# Mouse_Version_2.net
KiCad netlist of a schematic drawn in EAGLE
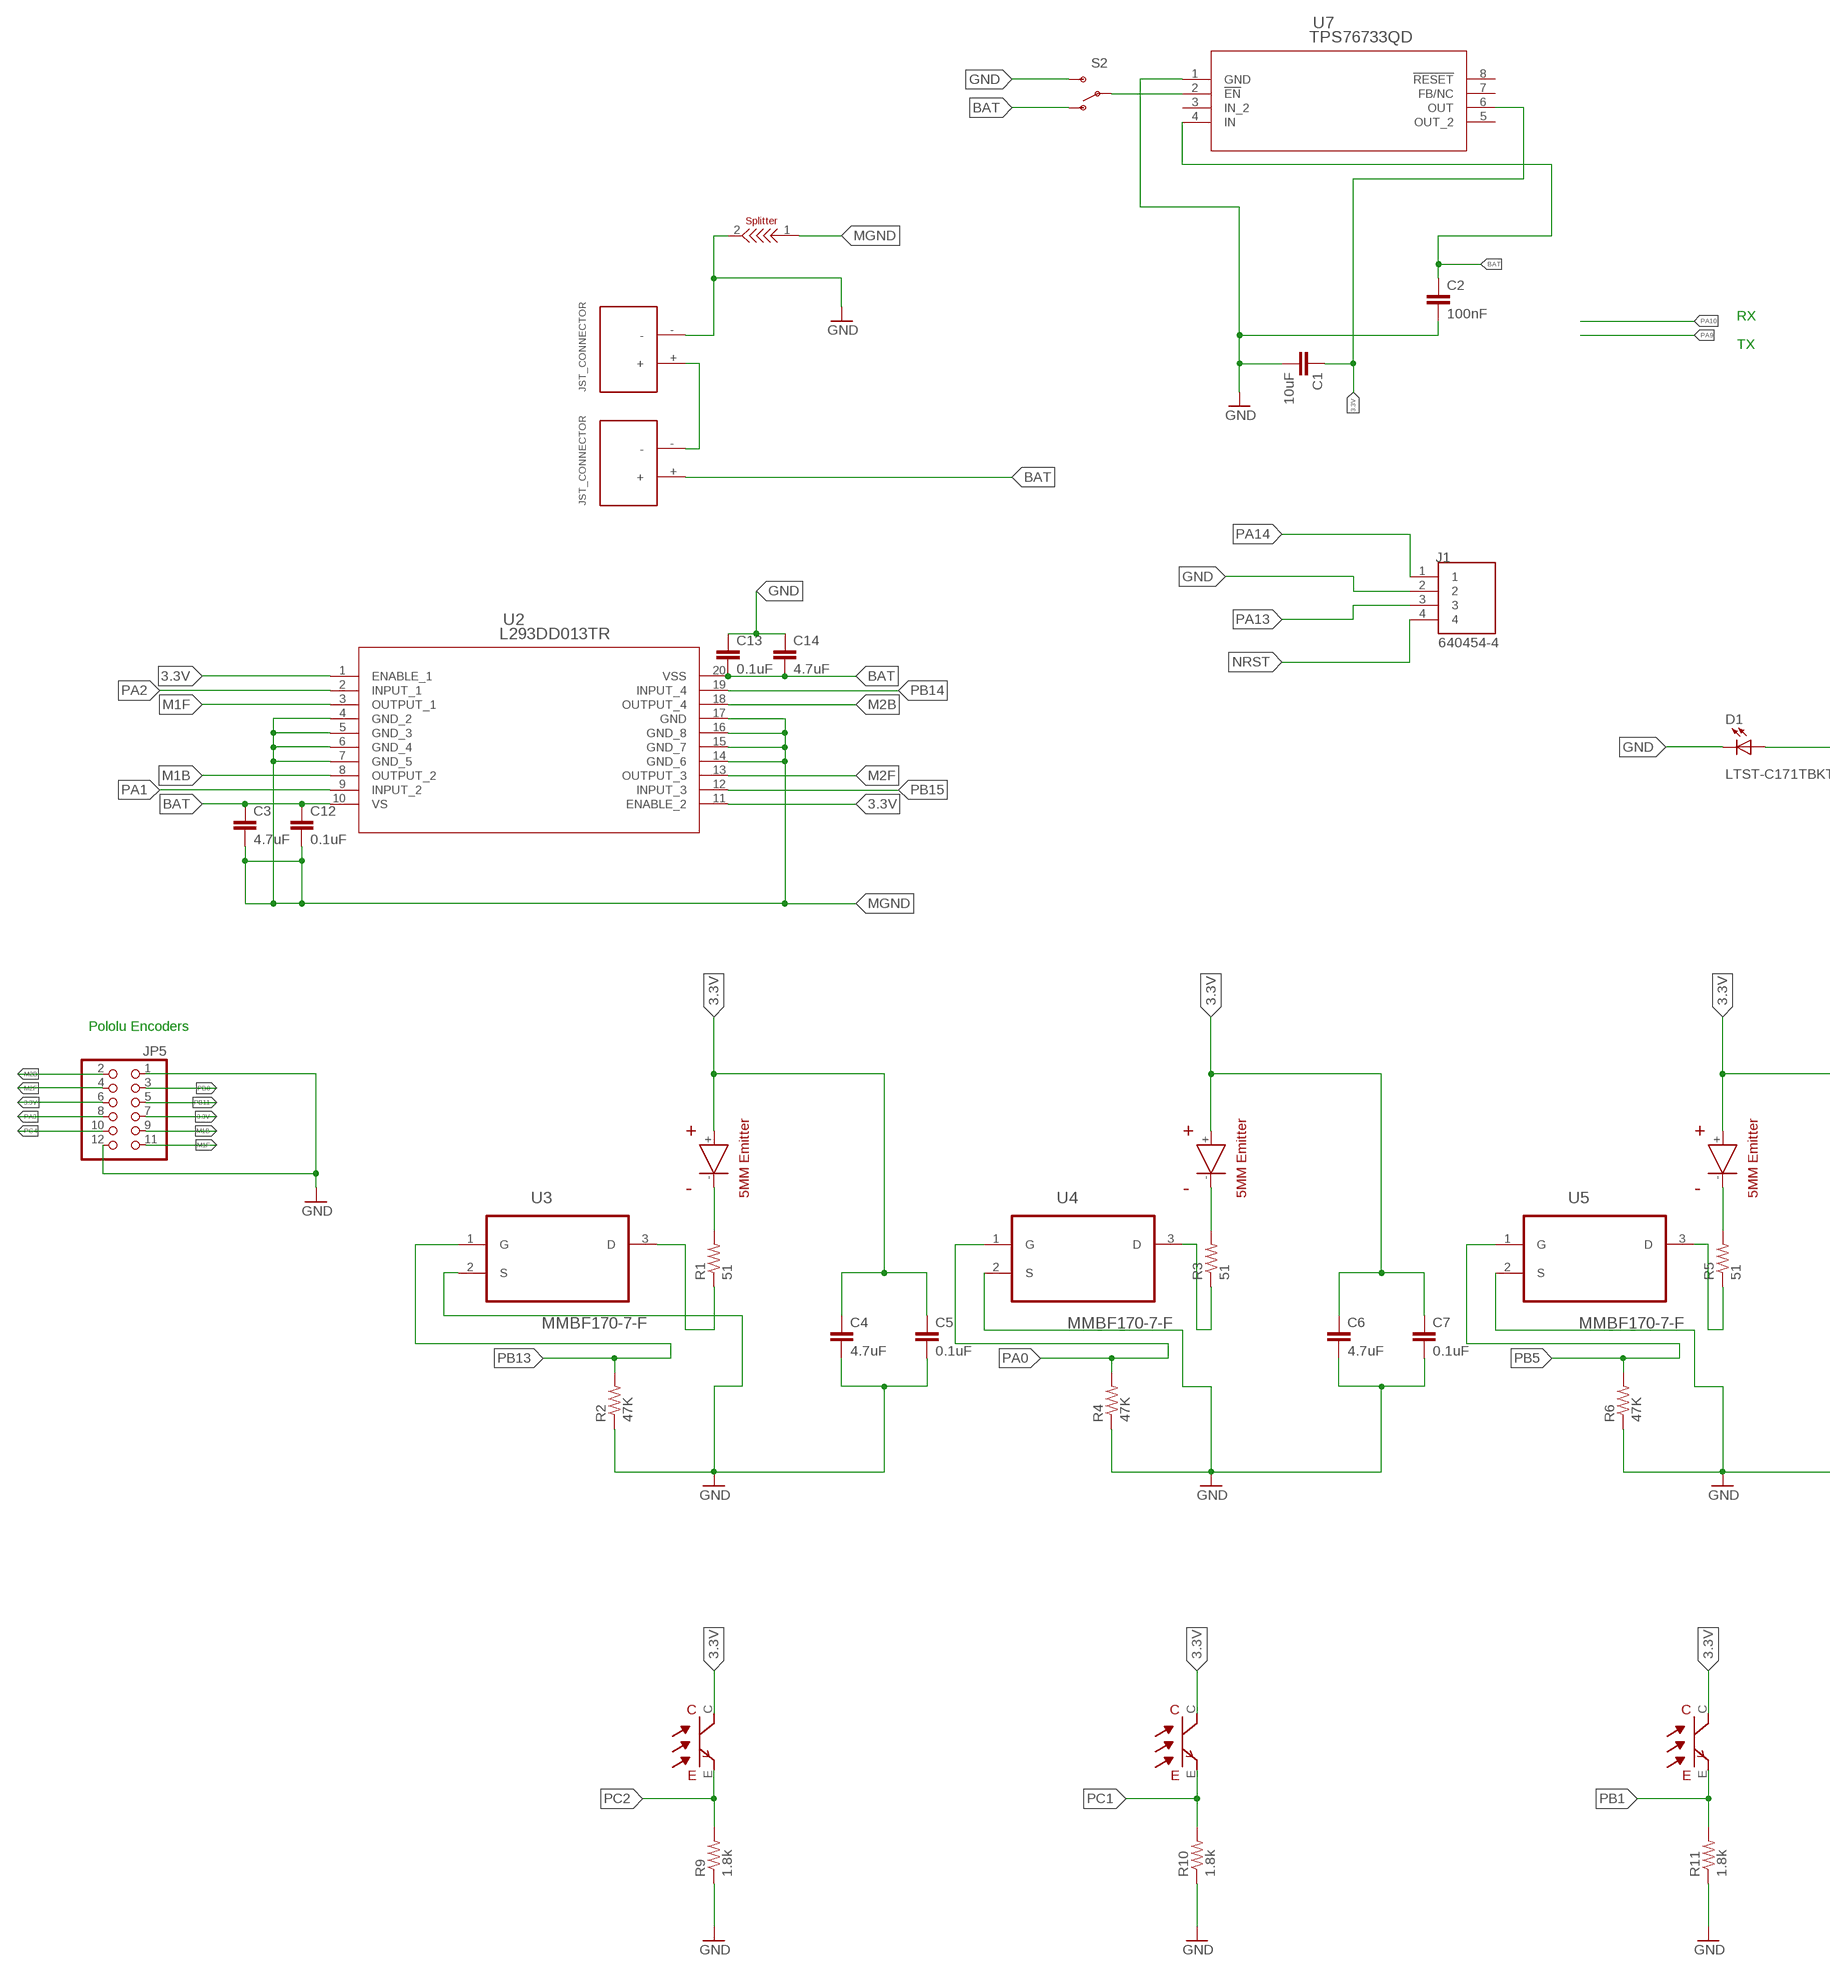
[diagram p0: schematic, sheet 1, part 1 of 2]
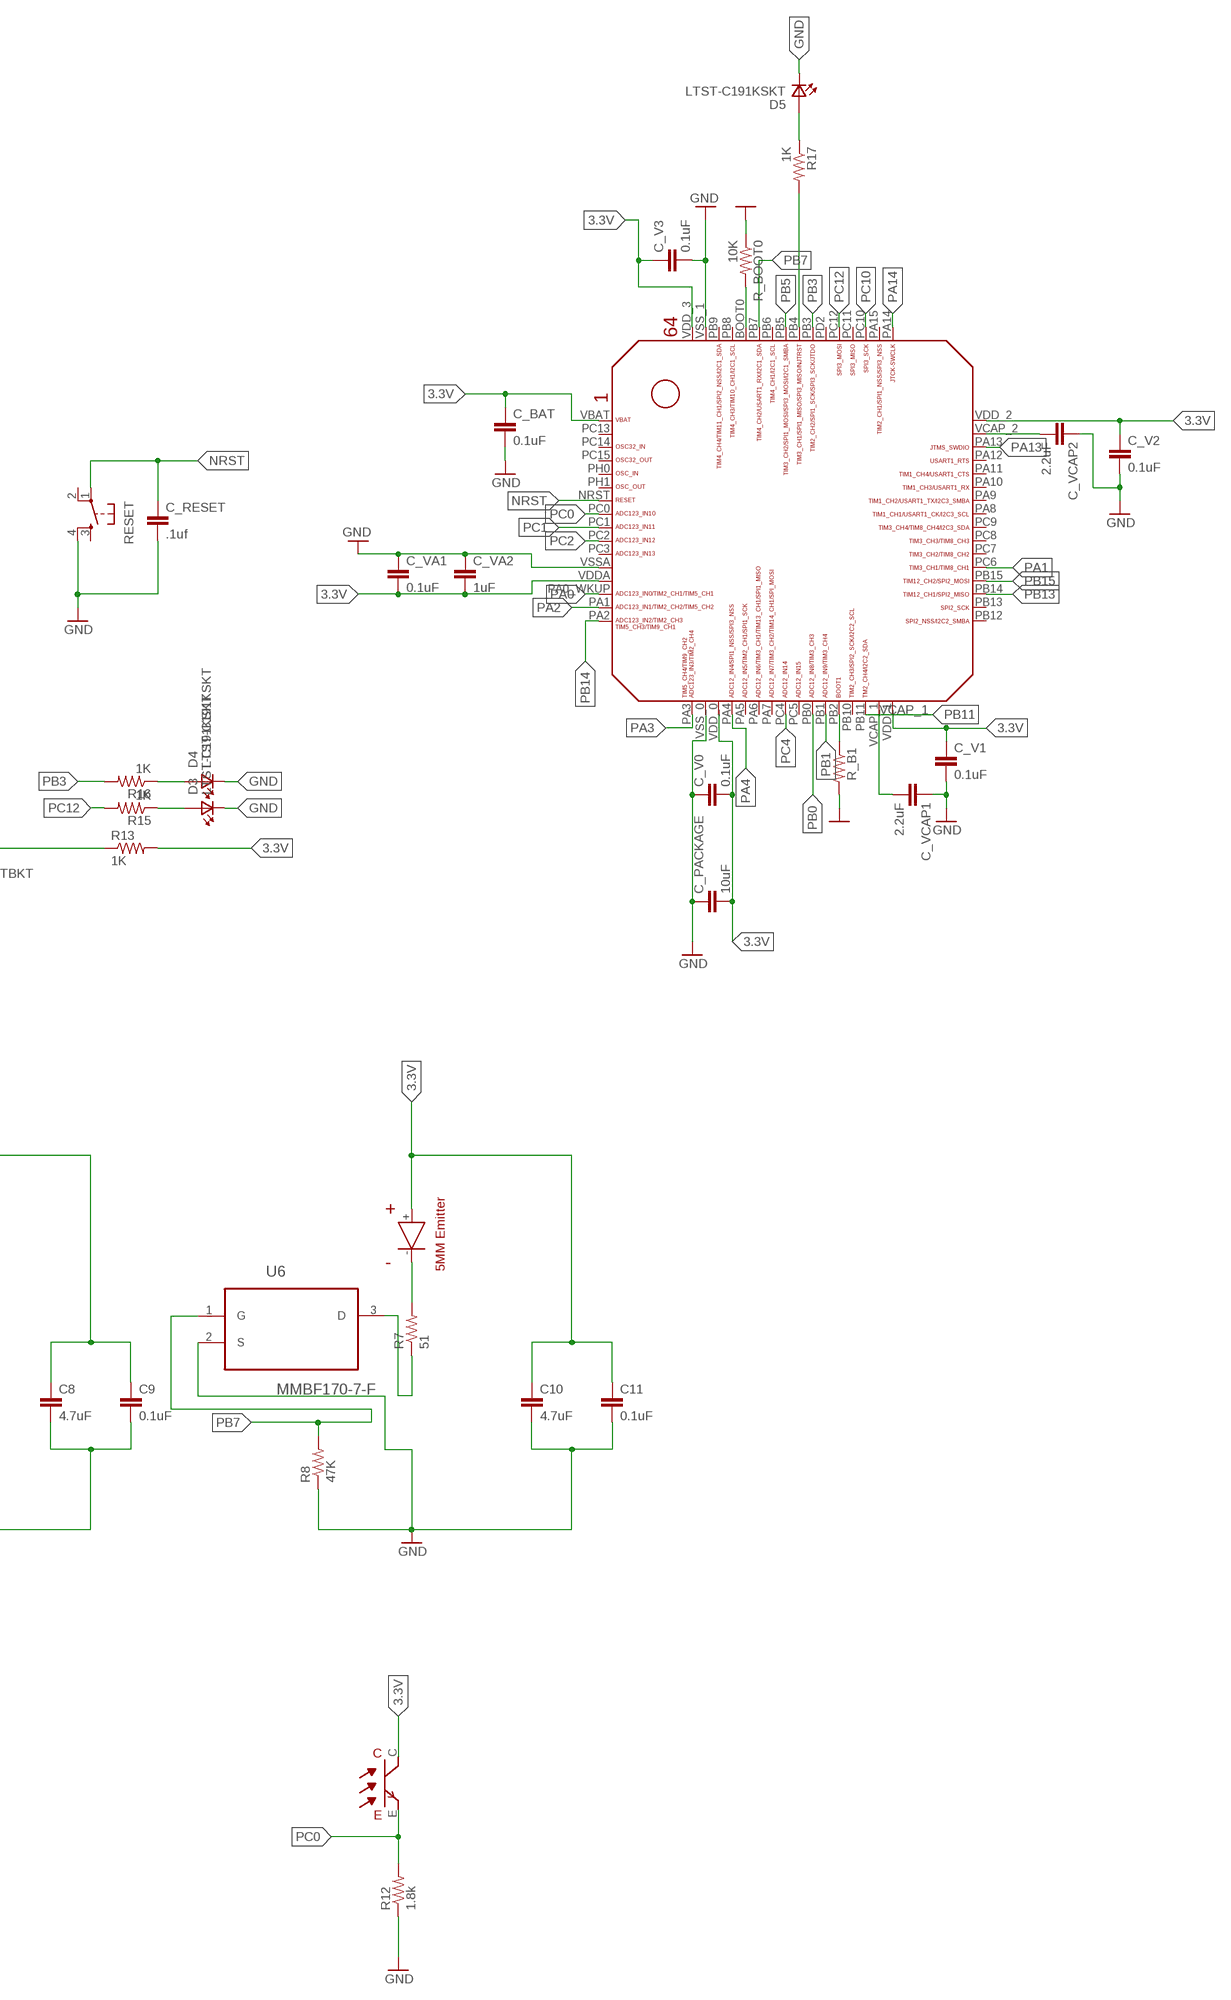
[diagram p1: schematic, sheet 1, part 2 of 2]

(export (version "E")
  (design (tool "Eeschema 10.0.6"))
  (components
    (comp (ref "C1")
      (value "10uF")
      (footprint "eagle-import:0603-CAP")
      (libsource (lib "eagle-import") (part "CAP0603-CAP"))
    )
    (comp (ref "C2")
      (value "100nF")
      (footprint "eagle-import:0603-CAP")
      (libsource (lib "eagle-import") (part "CAP0603-CAP"))
    )
    (comp (ref "C3")
      (value "4.7uF")
      (footprint "eagle-import:0603-CAP")
      (libsource (lib "eagle-import") (part "CAP0603-CAP"))
    )
    (comp (ref "C4")
      (value "4.7uF")
      (footprint "eagle-import:C1206")
      (libsource (lib "eagle-import") (part "C-EUC1206"))
    )
    (comp (ref "C5")
      (value "0.1uF")
      (footprint "eagle-import:C1206")
      (libsource (lib "eagle-import") (part "C-EUC1206"))
    )
    (comp (ref "C6")
      (value "4.7uF")
      (footprint "eagle-import:C1206")
      (libsource (lib "eagle-import") (part "C-EUC1206"))
    )
    (comp (ref "C7")
      (value "0.1uF")
      (footprint "eagle-import:C1206")
      (libsource (lib "eagle-import") (part "C-EUC1206"))
    )
    (comp (ref "C8")
      (value "4.7uF")
      (footprint "eagle-import:C1206")
      (libsource (lib "eagle-import") (part "C-EUC1206"))
    )
    (comp (ref "C9")
      (value "0.1uF")
      (footprint "eagle-import:C1206")
      (libsource (lib "eagle-import") (part "C-EUC1206"))
    )
    (comp (ref "C10")
      (value "4.7uF")
      (footprint "eagle-import:C1206")
      (libsource (lib "eagle-import") (part "C-EUC1206"))
    )
    (comp (ref "C11")
      (value "0.1uF")
      (footprint "eagle-import:C1206")
      (libsource (lib "eagle-import") (part "C-EUC1206"))
    )
    (comp (ref "C12")
      (value "0.1uF")
      (footprint "eagle-import:0603-CAP")
      (libsource (lib "eagle-import") (part "CAP0603-CAP"))
    )
    (comp (ref "C13")
      (value "0.1uF")
      (footprint "eagle-import:0603-CAP")
      (libsource (lib "eagle-import") (part "CAP0603-CAP"))
    )
    (comp (ref "C14")
      (value "4.7uF")
      (footprint "eagle-import:0603-CAP")
      (libsource (lib "eagle-import") (part "CAP0603-CAP"))
    )
    (comp (ref "C_BAT")
      (value "0.1uF")
      (footprint "eagle-import:0603-CAP")
      (libsource (lib "eagle-import") (part "CAP0603-CAP"))
    )
    (comp (ref "C_PACKAGE")
      (value "10uF")
      (footprint "eagle-import:0603-CAP")
      (libsource (lib "eagle-import") (part "CAP0603-CAP"))
    )
    (comp (ref "C_RESET")
      (value ".1uf")
      (footprint "eagle-import:0603")
      (libsource (lib "eagle-import") (part "10NF-0603-50V-10%"))
    )
    (comp (ref "C_V0")
      (value "0.1uF")
      (footprint "eagle-import:0603-CAP")
      (libsource (lib "eagle-import") (part "CAP0603-CAP"))
    )
    (comp (ref "C_V1")
      (value "0.1uF")
      (footprint "eagle-import:0603-CAP")
      (libsource (lib "eagle-import") (part "CAP0603-CAP"))
    )
    (comp (ref "C_V2")
      (value "0.1uF")
      (footprint "eagle-import:0603-CAP")
      (libsource (lib "eagle-import") (part "CAP0603-CAP"))
    )
    (comp (ref "C_V3")
      (value "0.1uF")
      (footprint "eagle-import:0603-CAP")
      (libsource (lib "eagle-import") (part "CAP0603-CAP"))
    )
    (comp (ref "C_VA1")
      (value "0.1uF")
      (footprint "eagle-import:0603-CAP")
      (libsource (lib "eagle-import") (part "CAP0603-CAP"))
    )
    (comp (ref "C_VA2")
      (value "1uF")
      (footprint "eagle-import:0603-CAP")
      (libsource (lib "eagle-import") (part "CAP0603-CAP"))
    )
    (comp (ref "C_VCAP1")
      (value "2.2uF")
      (footprint "eagle-import:0603-CAP")
      (libsource (lib "eagle-import") (part "CAP0603-CAP"))
    )
    (comp (ref "C_VCAP2")
      (value "2.2uF")
      (footprint "eagle-import:0603-CAP")
      (libsource (lib "eagle-import") (part "CAP0603-CAP"))
    )
    (comp (ref "D1")
      (value "LTST-C171TBKT")
      (footprint "eagle-import:DIOC200X125X110")
      (fields (field (name "DIGI-KEY_PART_NUMBER") "160-1645-1-ND") (field (name "MF") "Lite-On Inc."))
      (libsource (lib "eagle-import") (part "LTST-C171TBKT"))
    )
    (comp (ref "D3")
      (value "LTST-C191KSKT")
      (footprint "eagle-import:0603")
      (fields (field (name "DIGI-KEY_PART_NUMBER") "160-1448-1-ND") (field (name "MF") "Lite-On Inc."))
      (libsource (lib "eagle-import") (part "LTST-C191KSKT"))
    )
    (comp (ref "D4")
      (value "LTST-C191KSKT")
      (footprint "eagle-import:0603")
      (fields (field (name "DIGI-KEY_PART_NUMBER") "160-1448-1-ND") (field (name "MF") "Lite-On Inc."))
      (libsource (lib "eagle-import") (part "LTST-C191KSKT"))
    )
    (comp (ref "D5")
      (value "LTST-C191KSKT")
      (footprint "eagle-import:0603")
      (fields (field (name "DIGI-KEY_PART_NUMBER") "160-1448-1-ND") (field (name "MF") "Lite-On Inc."))
      (libsource (lib "eagle-import") (part "LTST-C191KSKT"))
    )
    (comp (ref "J1")
      (value "640454-4")
      (footprint "eagle-import:TE_640454-4")
      (fields (field (name "DIGI-KEY_PART_NUMBER") "A19431-ND") (field (name "MF") "TE Connectivity"))
      (libsource (lib "eagle-import") (part "640454-4"))
    )
    (comp (ref "JP5")
      (value "PINHD-2X6")
      (footprint "eagle-import:2X06")
      (libsource (lib "eagle-import") (part "PINHD-2X6"))
    )
    (comp (ref "R1")
      (value "51")
      (footprint "eagle-import:R0603")
      (libsource (lib "eagle-import") (part "R-US_R0603"))
    )
    (comp (ref "R2")
      (value "47K")
      (footprint "eagle-import:R0603")
      (libsource (lib "eagle-import") (part "R-US_R0603"))
    )
    (comp (ref "R3")
      (value "51")
      (footprint "eagle-import:R0603")
      (libsource (lib "eagle-import") (part "R-US_R0603"))
    )
    (comp (ref "R4")
      (value "47K")
      (footprint "eagle-import:R0603")
      (libsource (lib "eagle-import") (part "R-US_R0603"))
    )
    (comp (ref "R5")
      (value "51")
      (footprint "eagle-import:R0603")
      (libsource (lib "eagle-import") (part "R-US_R0603"))
    )
    (comp (ref "R6")
      (value "47K")
      (footprint "eagle-import:R0603")
      (libsource (lib "eagle-import") (part "R-US_R0603"))
    )
    (comp (ref "R7")
      (value "51")
      (footprint "eagle-import:R0603")
      (libsource (lib "eagle-import") (part "R-US_R0603"))
    )
    (comp (ref "R8")
      (value "47K")
      (footprint "eagle-import:R0603")
      (libsource (lib "eagle-import") (part "R-US_R0603"))
    )
    (comp (ref "R9")
      (value "1.8k")
      (footprint "eagle-import:R0603")
      (libsource (lib "eagle-import") (part "R-US_R0603"))
    )
    (comp (ref "R10")
      (value "1.8k")
      (footprint "eagle-import:R0603")
      (libsource (lib "eagle-import") (part "R-US_R0603"))
    )
    (comp (ref "R11")
      (value "1.8k")
      (footprint "eagle-import:R0603")
      (libsource (lib "eagle-import") (part "R-US_R0603"))
    )
    (comp (ref "R12")
      (value "1.8k")
      (footprint "eagle-import:R0603")
      (libsource (lib "eagle-import") (part "R-US_R0603"))
    )
    (comp (ref "R13")
      (value "1K")
      (footprint "eagle-import:R0603")
      (libsource (lib "eagle-import") (part "R-US_R0603"))
    )
    (comp (ref "R15")
      (value "1K")
      (footprint "eagle-import:R0603")
      (libsource (lib "eagle-import") (part "R-US_R0603"))
    )
    (comp (ref "R16")
      (value "1K")
      (footprint "eagle-import:R0603")
      (libsource (lib "eagle-import") (part "R-US_R0603"))
    )
    (comp (ref "R17")
      (value "1K")
      (footprint "eagle-import:R0603")
      (libsource (lib "eagle-import") (part "R-US_R0603"))
    )
    (comp (ref "RESET")
      (value "TAC_SWITCHPTH")
      (footprint "eagle-import:TACTILE-PTH")
      (libsource (lib "eagle-import") (part "TAC_SWITCHPTH"))
    )
    (comp (ref "R_B1")
      (value "10K")
      (footprint "eagle-import:0603-RES")
      (libsource (lib "eagle-import") (part "RESISTOR0603"))
    )
    (comp (ref "R_BOOT0")
      (value "10K")
      (footprint "eagle-import:0603-RES")
      (libsource (lib "eagle-import") (part "RESISTOR0603"))
    )
    (comp (ref "S2")
      (value "SWITCH-SPSTPTH")
      (footprint "eagle-import:SWITCH-SPDT")
      (libsource (lib "eagle-import") (part "SWITCH-SPSTPTH"))
    )
    (comp (ref "U$1")
      (value "JST_CONNECTOR_FEMALE")
      (footprint "eagle-import:JST_CONNECTOR_FEMALE")
      (libsource (lib "eagle-import") (part "JST_CONNECTOR_FEMALE"))
    )
    (comp (ref "U$2")
      (value "JST_CONNECTOR_FEMALE")
      (footprint "eagle-import:JST_CONNECTOR_FEMALE")
      (libsource (lib "eagle-import") (part "JST_CONNECTOR_FEMALE"))
    )
    (comp (ref "U$3")
      (value "SPLITTER")
      (footprint "eagle-import:SPLITTER")
      (libsource (lib "eagle-import") (part "SPLITTER"))
    )
    (comp (ref "U$4")
      (value "RECEIVER")
      (footprint "eagle-import:RECEIVER")
      (libsource (lib "eagle-import") (part "RECEIVER"))
    )
    (comp (ref "U$5")
      (value "EMITTER")
      (footprint "eagle-import:EMITTER")
      (libsource (lib "eagle-import") (part "EMITTER"))
    )
    (comp (ref "U$6")
      (value "EMITTER")
      (footprint "eagle-import:EMITTER")
      (libsource (lib "eagle-import") (part "EMITTER"))
    )
    (comp (ref "U$7")
      (value "EMITTER")
      (footprint "eagle-import:EMITTER")
      (libsource (lib "eagle-import") (part "EMITTER"))
    )
    (comp (ref "U$8")
      (value "EMITTER")
      (footprint "eagle-import:EMITTER")
      (libsource (lib "eagle-import") (part "EMITTER"))
    )
    (comp (ref "U$9")
      (value "STM32F405/415_LQFP64")
      (footprint "eagle-import:STM32F405_415_LQFP64")
      (libsource (lib "eagle-import") (part "STM32F405/415_LQFP64"))
    )
    (comp (ref "U$15")
      (value "RECEIVER")
      (footprint "eagle-import:RECEIVER")
      (libsource (lib "eagle-import") (part "RECEIVER"))
    )
    (comp (ref "U$18")
      (value "RECEIVER")
      (footprint "eagle-import:RECEIVER")
      (libsource (lib "eagle-import") (part "RECEIVER"))
    )
    (comp (ref "U$19")
      (value "RECEIVER")
      (footprint "eagle-import:RECEIVER")
      (libsource (lib "eagle-import") (part "RECEIVER"))
    )
    (comp (ref "U2")
      (value "L293DD013TR")
      (footprint "eagle-import:SO-20")
      (libsource (lib "eagle-import") (part "L293DD013TR"))
    )
    (comp (ref "U3")
      (value "MMBF170-7-F")
      (footprint "eagle-import:SOT103P240X110-3N")
      (fields (field (name "MF") "Diodes Inc."))
      (libsource (lib "eagle-import") (part "MMBF170-7-F"))
    )
    (comp (ref "U4")
      (value "MMBF170-7-F")
      (footprint "eagle-import:SOT103P240X110-3N")
      (fields (field (name "MF") "Diodes Inc."))
      (libsource (lib "eagle-import") (part "MMBF170-7-F"))
    )
    (comp (ref "U5")
      (value "MMBF170-7-F")
      (footprint "eagle-import:SOT103P240X110-3N")
      (fields (field (name "MF") "Diodes Inc."))
      (libsource (lib "eagle-import") (part "MMBF170-7-F"))
    )
    (comp (ref "U6")
      (value "MMBF170-7-F")
      (footprint "eagle-import:SOT103P240X110-3N")
      (fields (field (name "MF") "Diodes Inc."))
      (libsource (lib "eagle-import") (part "MMBF170-7-F"))
    )
    (comp (ref "U7")
      (value "TPS76733QD")
      (footprint "eagle-import:D8")
      (libsource (lib "eagle-import") (part "TPS76733QD"))
    )
  )
  (nets
    (net (code "1") (name "/VCAP_1") (class "Default")
      (node (ref "C_VCAP1") (pin "2") (pinfunction "2_2") (pintype "passive"))
      (node (ref "U$9") (pin "VCAP_1") (pinfunction "VCAP_1_VCAP_1") (pintype "bidirectional"))
    )
    (net (code "2") (name "3.3V") (class "Default")
      (node (ref "C1") (pin "1") (pinfunction "1_1") (pintype "passive"))
      (node (ref "C10") (pin "1") (pinfunction "1_1") (pintype "passive"))
      (node (ref "C11") (pin "1") (pinfunction "1_1") (pintype "passive"))
      (node (ref "C4") (pin "1") (pinfunction "1_1") (pintype "passive"))
      (node (ref "C5") (pin "1") (pinfunction "1_1") (pintype "passive"))
      (node (ref "C6") (pin "1") (pinfunction "1_1") (pintype "passive"))
      (node (ref "C7") (pin "1") (pinfunction "1_1") (pintype "passive"))
      (node (ref "C8") (pin "1") (pinfunction "1_1") (pintype "passive"))
      (node (ref "C9") (pin "1") (pinfunction "1_1") (pintype "passive"))
      (node (ref "C_BAT") (pin "1") (pinfunction "1_1") (pintype "passive"))
      (node (ref "C_PACKAGE") (pin "2") (pinfunction "2_2") (pintype "passive"))
      (node (ref "C_V0") (pin "2") (pinfunction "2_2") (pintype "passive"))
      (node (ref "C_V1") (pin "1") (pinfunction "1_1") (pintype "passive"))
      (node (ref "C_V2") (pin "1") (pinfunction "1_1") (pintype "passive"))
      (node (ref "C_V3") (pin "1") (pinfunction "1_1") (pintype "passive"))
      (node (ref "C_VA1") (pin "2") (pinfunction "2_2") (pintype "passive"))
      (node (ref "C_VA2") (pin "2") (pinfunction "2_2") (pintype "passive"))
      (node (ref "JP5") (pin "6") (pinfunction "6_6") (pintype "passive"))
      (node (ref "JP5") (pin "7") (pinfunction "7_7") (pintype "passive"))
      (node (ref "R13") (pin "2") (pinfunction "2_2") (pintype "passive"))
      (node (ref "U$15") (pin "C") (pinfunction "C_C") (pintype "bidirectional"))
      (node (ref "U$18") (pin "C") (pinfunction "C_C") (pintype "bidirectional"))
      (node (ref "U$19") (pin "C") (pinfunction "C_C") (pintype "bidirectional"))
      (node (ref "U$4") (pin "C") (pinfunction "C_C") (pintype "bidirectional"))
      (node (ref "U$5") (pin "+") (pinfunction "+_+") (pintype "bidirectional"))
      (node (ref "U$6") (pin "+") (pinfunction "+_+") (pintype "bidirectional"))
      (node (ref "U$7") (pin "+") (pinfunction "+_+") (pintype "bidirectional"))
      (node (ref "U$8") (pin "+") (pinfunction "+_+") (pintype "bidirectional"))
      (node (ref "U$9") (pin "VBAT") (pinfunction "VBAT_VBAT") (pintype "bidirectional"))
      (node (ref "U$9") (pin "VDDA") (pinfunction "VDDA_VDDA") (pintype "bidirectional"))
      (node (ref "U$9") (pin "VDD_0") (pinfunction "VDD_0_VDD_0") (pintype "bidirectional"))
      (node (ref "U$9") (pin "VDD_1") (pinfunction "VDD_1_VDD_1") (pintype "bidirectional"))
      (node (ref "U$9") (pin "VDD_2") (pinfunction "VDD_2_VDD_2") (pintype "bidirectional"))
      (node (ref "U$9") (pin "VDD_3") (pinfunction "VDD_3_VDD_3") (pintype "bidirectional"))
      (node (ref "U2") (pin "1") (pinfunction "ENABLE_1_1") (pintype "input"))
      (node (ref "U2") (pin "11") (pinfunction "ENABLE_2_11") (pintype "input"))
      (node (ref "U7") (pin "6") (pinfunction "OUT_6") (pintype "output"))
    )
    (net (code "3") (name "BAT") (class "Default")
      (node (ref "C12") (pin "1") (pinfunction "1_1") (pintype "passive"))
      (node (ref "C13") (pin "2") (pinfunction "2_2") (pintype "passive"))
      (node (ref "C14") (pin "2") (pinfunction "2_2") (pintype "passive"))
      (node (ref "C2") (pin "1") (pinfunction "1_1") (pintype "passive"))
      (node (ref "C3") (pin "1") (pinfunction "1_1") (pintype "passive"))
      (node (ref "S2") (pin "1") (pinfunction "O_1") (pintype "passive"))
      (node (ref "U$2") (pin "+") (pinfunction "+_+") (pintype "bidirectional"))
      (node (ref "U2") (pin "10") (pinfunction "VS_10") (pintype "passive"))
      (node (ref "U2") (pin "20") (pinfunction "VSS_20") (pintype "passive"))
      (node (ref "U7") (pin "4") (pinfunction "IN_4") (pintype "input"))
    )
    (net (code "4") (name "GND") (class "Default")
      (node (ref "C1") (pin "2") (pinfunction "2_2") (pintype "passive"))
      (node (ref "C10") (pin "2") (pinfunction "2_2") (pintype "passive"))
      (node (ref "C11") (pin "2") (pinfunction "2_2") (pintype "passive"))
      (node (ref "C13") (pin "1") (pinfunction "1_1") (pintype "passive"))
      (node (ref "C14") (pin "1") (pinfunction "1_1") (pintype "passive"))
      (node (ref "C2") (pin "2") (pinfunction "2_2") (pintype "passive"))
      (node (ref "C4") (pin "2") (pinfunction "2_2") (pintype "passive"))
      (node (ref "C5") (pin "2") (pinfunction "2_2") (pintype "passive"))
      (node (ref "C6") (pin "2") (pinfunction "2_2") (pintype "passive"))
      (node (ref "C7") (pin "2") (pinfunction "2_2") (pintype "passive"))
      (node (ref "C8") (pin "2") (pinfunction "2_2") (pintype "passive"))
      (node (ref "C9") (pin "2") (pinfunction "2_2") (pintype "passive"))
      (node (ref "C_BAT") (pin "2") (pinfunction "2_2") (pintype "passive"))
      (node (ref "C_PACKAGE") (pin "1") (pinfunction "1_1") (pintype "passive"))
      (node (ref "C_RESET") (pin "2") (pinfunction "2_2") (pintype "passive"))
      (node (ref "C_V0") (pin "1") (pinfunction "1_1") (pintype "passive"))
      (node (ref "C_V1") (pin "2") (pinfunction "2_2") (pintype "passive"))
      (node (ref "C_V2") (pin "2") (pinfunction "2_2") (pintype "passive"))
      (node (ref "C_V3") (pin "2") (pinfunction "2_2") (pintype "passive"))
      (node (ref "C_VA1") (pin "1") (pinfunction "1_1") (pintype "passive"))
      (node (ref "C_VA2") (pin "1") (pinfunction "1_1") (pintype "passive"))
      (node (ref "C_VCAP1") (pin "1") (pinfunction "1_1") (pintype "passive"))
      (node (ref "C_VCAP2") (pin "1") (pinfunction "1_1") (pintype "passive"))
      (node (ref "D1") (pin "-") (pinfunction "-_-") (pintype "passive"))
      (node (ref "D3") (pin "1") (pinfunction "K2_1") (pintype "passive"))
      (node (ref "D4") (pin "1") (pinfunction "K2_1") (pintype "passive"))
      (node (ref "D5") (pin "1") (pinfunction "K2_1") (pintype "passive"))
      (node (ref "J1") (pin "2") (pinfunction "2_2") (pintype "passive"))
      (node (ref "JP5") (pin "1") (pinfunction "1_1") (pintype "passive"))
      (node (ref "JP5") (pin "12") (pinfunction "12_12") (pintype "passive"))
      (node (ref "R10") (pin "1") (pinfunction "1_1") (pintype "passive"))
      (node (ref "R11") (pin "1") (pinfunction "1_1") (pintype "passive"))
      (node (ref "R12") (pin "1") (pinfunction "1_1") (pintype "passive"))
      (node (ref "R2") (pin "1") (pinfunction "1_1") (pintype "passive"))
      (node (ref "R4") (pin "1") (pinfunction "1_1") (pintype "passive"))
      (node (ref "R6") (pin "1") (pinfunction "1_1") (pintype "passive"))
      (node (ref "R8") (pin "1") (pinfunction "1_1") (pintype "passive"))
      (node (ref "R9") (pin "1") (pinfunction "1_1") (pintype "passive"))
      (node (ref "RESET") (pin "4") (pinfunction "4_4") (pintype "passive"))
      (node (ref "R_B1") (pin "2") (pinfunction "2_2") (pintype "passive"))
      (node (ref "R_BOOT0") (pin "1") (pinfunction "1_1") (pintype "passive"))
      (node (ref "S2") (pin "3") (pinfunction "S_3") (pintype "passive"))
      (node (ref "U$1") (pin "-") (pinfunction "-_-") (pintype "bidirectional"))
      (node (ref "U$3") (pin "2") (pinfunction "2_2") (pintype "bidirectional"))
      (node (ref "U$9") (pin "VSSA") (pinfunction "VSSA_VSSA") (pintype "bidirectional"))
      (node (ref "U$9") (pin "VSS_0") (pinfunction "VSS_0_VSS_0") (pintype "bidirectional"))
      (node (ref "U$9") (pin "VSS_1") (pinfunction "VSS_1_VSS_1") (pintype "bidirectional"))
      (node (ref "U3") (pin "2") (pinfunction "S_2") (pintype "passive"))
      (node (ref "U4") (pin "2") (pinfunction "S_2") (pintype "passive"))
      (node (ref "U5") (pin "2") (pinfunction "S_2") (pintype "passive"))
      (node (ref "U6") (pin "2") (pinfunction "S_2") (pintype "passive"))
      (node (ref "U7") (pin "1") (pinfunction "GND_1") (pintype "power_in"))
    )
    (net (code "5") (name "M1B") (class "Default")
      (node (ref "JP5") (pin "9") (pinfunction "9_9") (pintype "passive"))
      (node (ref "U2") (pin "8") (pinfunction "OUTPUT_2_8") (pintype "output"))
    )
    (net (code "6") (name "M1F") (class "Default")
      (node (ref "JP5") (pin "11") (pinfunction "11_11") (pintype "passive"))
      (node (ref "U2") (pin "3") (pinfunction "OUTPUT_1_3") (pintype "output"))
    )
    (net (code "7") (name "M2B") (class "Default")
      (node (ref "JP5") (pin "2") (pinfunction "2_2") (pintype "passive"))
      (node (ref "U2") (pin "18") (pinfunction "OUTPUT_4_18") (pintype "output"))
    )
    (net (code "8") (name "M2F") (class "Default")
      (node (ref "JP5") (pin "4") (pinfunction "4_4") (pintype "passive"))
      (node (ref "U2") (pin "13") (pinfunction "OUTPUT_3_13") (pintype "output"))
    )
    (net (code "9") (name "MGND") (class "Default")
      (node (ref "C12") (pin "2") (pinfunction "2_2") (pintype "passive"))
      (node (ref "C3") (pin "2") (pinfunction "2_2") (pintype "passive"))
      (node (ref "U$3") (pin "1") (pinfunction "1_1") (pintype "bidirectional"))
      (node (ref "U2") (pin "14") (pinfunction "GND_6_14") (pintype "passive"))
      (node (ref "U2") (pin "15") (pinfunction "GND_7_15") (pintype "passive"))
      (node (ref "U2") (pin "16") (pinfunction "GND_8_16") (pintype "passive"))
      (node (ref "U2") (pin "17") (pinfunction "GND_17") (pintype "passive"))
      (node (ref "U2") (pin "4") (pinfunction "GND_2_4") (pintype "passive"))
      (node (ref "U2") (pin "5") (pinfunction "GND_3_5") (pintype "passive"))
      (node (ref "U2") (pin "6") (pinfunction "GND_4_6") (pintype "passive"))
      (node (ref "U2") (pin "7") (pinfunction "GND_5_7") (pintype "passive"))
    )
    (net (code "10") (name "NRST") (class "Default")
      (node (ref "C_RESET") (pin "1") (pinfunction "1_1") (pintype "passive"))
      (node (ref "J1") (pin "4") (pinfunction "4_4") (pintype "passive"))
      (node (ref "RESET") (pin "1") (pinfunction "1_1") (pintype "passive"))
      (node (ref "U$9") (pin "NRST") (pinfunction "NRST_NRST") (pintype "bidirectional"))
    )
    (net (code "11") (name "Net-(C_VCAP2-Pad2)") (class "Default")
      (node (ref "C_VCAP2") (pin "2") (pinfunction "2_2") (pintype "passive"))
      (node (ref "U$9") (pin "VCAP_2") (pinfunction "VCAP_2_VCAP_2") (pintype "bidirectional"))
    )
    (net (code "12") (name "Net-(D1-Pad+)") (class "Default")
      (node (ref "D1") (pin "+") (pinfunction "+_+") (pintype "passive"))
      (node (ref "R13") (pin "1") (pinfunction "1_1") (pintype "passive"))
    )
    (net (code "13") (name "Net-(D3-A2)") (class "Default")
      (node (ref "D3") (pin "2") (pinfunction "A2_2") (pintype "passive"))
      (node (ref "R15") (pin "1") (pinfunction "1_1") (pintype "passive"))
    )
    (net (code "14") (name "Net-(D4-A2)") (class "Default")
      (node (ref "D4") (pin "2") (pinfunction "A2_2") (pintype "passive"))
      (node (ref "R16") (pin "1") (pinfunction "1_1") (pintype "passive"))
    )
    (net (code "15") (name "Net-(D5-A2)") (class "Default")
      (node (ref "D5") (pin "2") (pinfunction "A2_2") (pintype "passive"))
      (node (ref "R17") (pin "1") (pinfunction "1_1") (pintype "passive"))
    )
    (net (code "16") (name "Net-(R1-Pad2)") (class "Default")
      (node (ref "R1") (pin "2") (pinfunction "2_2") (pintype "passive"))
      (node (ref "U$5") (pin "-") (pinfunction "-_-") (pintype "bidirectional"))
    )
    (net (code "17") (name "Net-(R3-Pad2)") (class "Default")
      (node (ref "R3") (pin "2") (pinfunction "2_2") (pintype "passive"))
      (node (ref "U$6") (pin "-") (pinfunction "-_-") (pintype "bidirectional"))
    )
    (net (code "18") (name "Net-(R5-Pad2)") (class "Default")
      (node (ref "R5") (pin "2") (pinfunction "2_2") (pintype "passive"))
      (node (ref "U$7") (pin "-") (pinfunction "-_-") (pintype "bidirectional"))
    )
    (net (code "19") (name "Net-(R7-Pad2)") (class "Default")
      (node (ref "R7") (pin "2") (pinfunction "2_2") (pintype "passive"))
      (node (ref "U$8") (pin "-") (pinfunction "-_-") (pintype "bidirectional"))
    )
    (net (code "20") (name "Net-(R17-Pad2)") (class "Default")
      (node (ref "R17") (pin "2") (pinfunction "2_2") (pintype "passive"))
      (node (ref "U$9") (pin "PB4") (pinfunction "PB4_PB4") (pintype "bidirectional"))
    )
    (net (code "21") (name "Net-(R_B1-Pad1)") (class "Default")
      (node (ref "R_B1") (pin "1") (pinfunction "1_1") (pintype "passive"))
      (node (ref "U$9") (pin "PB2") (pinfunction "PB2_PB2") (pintype "bidirectional"))
    )
    (net (code "22") (name "Net-(R_BOOT0-Pad2)") (class "Default")
      (node (ref "R_BOOT0") (pin "2") (pinfunction "2_2") (pintype "passive"))
      (node (ref "U$9") (pin "BOOT0") (pinfunction "BOOT0_BOOT0") (pintype "bidirectional"))
    )
    (net (code "23") (name "Net-(S2-P)") (class "Default")
      (node (ref "S2") (pin "2") (pinfunction "P_2") (pintype "passive"))
      (node (ref "U7") (pin "2") (pinfunction "~{EN}_2") (pintype "input"))
    )
    (net (code "24") (name "Net-(U$1-Pad+)") (class "Default")
      (node (ref "U$1") (pin "+") (pinfunction "+_+") (pintype "bidirectional"))
      (node (ref "U$2") (pin "-") (pinfunction "-_-") (pintype "bidirectional"))
    )
    (net (code "25") (name "Net-(U3-D)") (class "Default")
      (node (ref "R1") (pin "1") (pinfunction "1_1") (pintype "passive"))
      (node (ref "U3") (pin "3") (pinfunction "D_3") (pintype "output"))
    )
    (net (code "26") (name "Net-(U4-D)") (class "Default")
      (node (ref "R3") (pin "1") (pinfunction "1_1") (pintype "passive"))
      (node (ref "U4") (pin "3") (pinfunction "D_3") (pintype "output"))
    )
    (net (code "27") (name "Net-(U5-D)") (class "Default")
      (node (ref "R5") (pin "1") (pinfunction "1_1") (pintype "passive"))
      (node (ref "U5") (pin "3") (pinfunction "D_3") (pintype "output"))
    )
    (net (code "28") (name "Net-(U6-D)") (class "Default")
      (node (ref "R7") (pin "1") (pinfunction "1_1") (pintype "passive"))
      (node (ref "U6") (pin "3") (pinfunction "D_3") (pintype "output"))
    )
    (net (code "29") (name "PA0") (class "Default")
      (node (ref "R4") (pin "2") (pinfunction "2_2") (pintype "passive"))
      (node (ref "U$9") (pin "PA0_WKUP") (pinfunction "PA0_AKUP_PA0_WKUP") (pintype "bidirectional"))
      (node (ref "U4") (pin "1") (pinfunction "G_1") (pintype "input"))
    )
    (net (code "30") (name "PA1") (class "Default")
      (node (ref "U$9") (pin "PC6") (pinfunction "PC6_PC6") (pintype "bidirectional"))
      (node (ref "U2") (pin "9") (pinfunction "INPUT_2_9") (pintype "input"))
    )
    (net (code "31") (name "PA2") (class "Default")
      (node (ref "U$9") (pin "PA1") (pinfunction "PA1_PA1") (pintype "bidirectional"))
      (node (ref "U2") (pin "2") (pinfunction "INPUT_1_2") (pintype "input"))
    )
    (net (code "32") (name "PA3") (class "Default")
      (node (ref "JP5") (pin "8") (pinfunction "8_8") (pintype "passive"))
      (node (ref "U$9") (pin "PA3") (pinfunction "PA3_PA3") (pintype "bidirectional"))
    )
    (net (code "33") (name "PA4") (class "Default")
      (node (ref "U$9") (pin "PA4") (pinfunction "PA4_PA4") (pintype "bidirectional"))
    )
    (net (code "36") (name "PA13") (class "Default")
      (node (ref "J1") (pin "3") (pinfunction "3_3") (pintype "passive"))
      (node (ref "U$9") (pin "PA13") (pinfunction "PA13_PA13") (pintype "bidirectional"))
    )
    (net (code "37") (name "PA14") (class "Default")
      (node (ref "J1") (pin "1") (pinfunction "1_1") (pintype "passive"))
      (node (ref "U$9") (pin "PA14") (pinfunction "PA14_PA14") (pintype "bidirectional"))
    )
    (net (code "38") (name "PB0") (class "Default")
      (node (ref "JP5") (pin "3") (pinfunction "3_3") (pintype "passive"))
      (node (ref "U$9") (pin "PB0") (pinfunction "PB0_PB0") (pintype "bidirectional"))
    )
    (net (code "39") (name "PB1") (class "Default")
      (node (ref "R11") (pin "2") (pinfunction "2_2") (pintype "passive"))
      (node (ref "U$15") (pin "E") (pinfunction "E_E") (pintype "bidirectional"))
      (node (ref "U$9") (pin "PB1") (pinfunction "PB1_PB1") (pintype "bidirectional"))
    )
    (net (code "40") (name "PB3") (class "Default")
      (node (ref "R16") (pin "2") (pinfunction "2_2") (pintype "passive"))
      (node (ref "U$9") (pin "PB3") (pinfunction "PB3_PB3") (pintype "bidirectional"))
    )
    (net (code "41") (name "PB5") (class "Default")
      (node (ref "R6") (pin "2") (pinfunction "2_2") (pintype "passive"))
      (node (ref "U$9") (pin "PB5") (pinfunction "PB5_PB5") (pintype "bidirectional"))
      (node (ref "U5") (pin "1") (pinfunction "G_1") (pintype "input"))
    )
    (net (code "42") (name "PB7") (class "Default")
      (node (ref "R8") (pin "2") (pinfunction "2_2") (pintype "passive"))
      (node (ref "U$9") (pin "PB7") (pinfunction "PB7_PB7") (pintype "bidirectional"))
      (node (ref "U6") (pin "1") (pinfunction "G_1") (pintype "input"))
    )
    (net (code "43") (name "PB11") (class "Default")
      (node (ref "JP5") (pin "5") (pinfunction "5_5") (pintype "passive"))
      (node (ref "U$9") (pin "PB11") (pinfunction "PB11_PB11") (pintype "bidirectional"))
    )
    (net (code "44") (name "PB13") (class "Default")
      (node (ref "R2") (pin "2") (pinfunction "2_2") (pintype "passive"))
      (node (ref "U$9") (pin "PB14") (pinfunction "PB14_PB14") (pintype "bidirectional"))
      (node (ref "U3") (pin "1") (pinfunction "G_1") (pintype "input"))
    )
    (net (code "45") (name "PB14") (class "Default")
      (node (ref "U$9") (pin "PA2") (pinfunction "PA2_PA2") (pintype "bidirectional"))
      (node (ref "U2") (pin "19") (pinfunction "INPUT_4_19") (pintype "input"))
    )
    (net (code "46") (name "PB15") (class "Default")
      (node (ref "U$9") (pin "PB15") (pinfunction "PB15_PB15") (pintype "bidirectional"))
      (node (ref "U2") (pin "12") (pinfunction "INPUT_3_12") (pintype "input"))
    )
    (net (code "47") (name "PC0") (class "Default")
      (node (ref "R12") (pin "2") (pinfunction "2_2") (pintype "passive"))
      (node (ref "U$4") (pin "E") (pinfunction "E_E") (pintype "bidirectional"))
      (node (ref "U$9") (pin "PC0") (pinfunction "PC0_PC0") (pintype "bidirectional"))
    )
    (net (code "48") (name "PC1") (class "Default")
      (node (ref "R10") (pin "2") (pinfunction "2_2") (pintype "passive"))
      (node (ref "U$18") (pin "E") (pinfunction "E_E") (pintype "bidirectional"))
      (node (ref "U$9") (pin "PC1") (pinfunction "PC1_PC1") (pintype "bidirectional"))
    )
    (net (code "49") (name "PC2") (class "Default")
      (node (ref "R9") (pin "2") (pinfunction "2_2") (pintype "passive"))
      (node (ref "U$19") (pin "E") (pinfunction "E_E") (pintype "bidirectional"))
      (node (ref "U$9") (pin "PC2") (pinfunction "PC2_PC2") (pintype "bidirectional"))
    )
    (net (code "50") (name "PC4") (class "Default")
      (node (ref "JP5") (pin "10") (pinfunction "10_10") (pintype "passive"))
      (node (ref "U$9") (pin "PC4") (pinfunction "PC4_PC4") (pintype "bidirectional"))
    )
    (net (code "51") (name "PC10") (class "Default")
      (node (ref "U$9") (pin "PC10") (pinfunction "PC10_PC10") (pintype "bidirectional"))
    )
    (net (code "52") (name "PC12") (class "Default")
      (node (ref "R15") (pin "2") (pinfunction "2_2") (pintype "passive"))
      (node (ref "U$9") (pin "PC12") (pinfunction "PC12_PC12") (pintype "bidirectional"))
    )
    (net (code "53") (name "unconnected-(RESET-Pad2)") (class "Default")
      (node (ref "RESET") (pin "2") (pinfunction "2_2") (pintype "passive"))
    )
    (net (code "54") (name "unconnected-(RESET-Pad3)") (class "Default")
      (node (ref "RESET") (pin "3") (pinfunction "3_3") (pintype "passive"))
    )
    (net (code "55") (name "unconnected-(U$9-PadPA5)") (class "Default")
      (node (ref "U$9") (pin "PA5") (pinfunction "PA5_PA5") (pintype "bidirectional"))
    )
    (net (code "56") (name "unconnected-(U$9-PadPA6)") (class "Default")
      (node (ref "U$9") (pin "PA6") (pinfunction "PA6_PA6") (pintype "bidirectional"))
    )
    (net (code "57") (name "unconnected-(U$9-PadPA7)") (class "Default")
      (node (ref "U$9") (pin "PA7") (pinfunction "PA7_PA7") (pintype "bidirectional"))
    )
    (net (code "58") (name "unconnected-(U$9-PadPA8)") (class "Default")
      (node (ref "U$9") (pin "PA8") (pinfunction "PA8_PA8") (pintype "bidirectional"))
    )
    (net (code "59") (name "unconnected-(U$9-PadPA9)") (class "Default")
      (node (ref "U$9") (pin "PA9") (pinfunction "PA9_PA9") (pintype "bidirectional"))
    )
    (net (code "60") (name "unconnected-(U$9-PadPA10)") (class "Default")
      (node (ref "U$9") (pin "PA10") (pinfunction "PA10_PA10") (pintype "bidirectional"))
    )
    (net (code "61") (name "unconnected-(U$9-PadPA11)") (class "Default")
      (node (ref "U$9") (pin "PA11") (pinfunction "PA11_PA11") (pintype "bidirectional"))
    )
    (net (code "62") (name "unconnected-(U$9-PadPA12)") (class "Default")
      (node (ref "U$9") (pin "PA12") (pinfunction "PA12_PA12") (pintype "bidirectional"))
    )
    (net (code "63") (name "unconnected-(U$9-PadPA15)") (class "Default")
      (node (ref "U$9") (pin "PA15") (pinfunction "PA15_PA15") (pintype "bidirectional"))
    )
    (net (code "64") (name "unconnected-(U$9-PadPB6)") (class "Default")
      (node (ref "U$9") (pin "PB6") (pinfunction "PB6_PB6") (pintype "bidirectional"))
    )
    (net (code "65") (name "unconnected-(U$9-PadPB8)") (class "Default")
      (node (ref "U$9") (pin "PB8") (pinfunction "PB8_PB8") (pintype "bidirectional"))
    )
    (net (code "66") (name "unconnected-(U$9-PadPB9)") (class "Default")
      (node (ref "U$9") (pin "PB9") (pinfunction "PB9_PB9") (pintype "bidirectional"))
    )
    (net (code "67") (name "unconnected-(U$9-PadPB10)") (class "Default")
      (node (ref "U$9") (pin "PB10") (pinfunction "PB10_PB10") (pintype "bidirectional"))
    )
    (net (code "68") (name "unconnected-(U$9-PadPB12)") (class "Default")
      (node (ref "U$9") (pin "PB12") (pinfunction "PB12_PB12") (pintype "bidirectional"))
    )
    (net (code "69") (name "unconnected-(U$9-PadPB13)") (class "Default")
      (node (ref "U$9") (pin "PB13") (pinfunction "PB13_PB13") (pintype "bidirectional"))
    )
    (net (code "70") (name "unconnected-(U$9-PadPC3)") (class "Default")
      (node (ref "U$9") (pin "PC3") (pinfunction "PC3_PC3") (pintype "bidirectional"))
    )
    (net (code "71") (name "unconnected-(U$9-PadPC5)") (class "Default")
      (node (ref "U$9") (pin "PC5") (pinfunction "PC5_PC5") (pintype "bidirectional"))
    )
    (net (code "72") (name "unconnected-(U$9-PadPC7)") (class "Default")
      (node (ref "U$9") (pin "PC7") (pinfunction "PC7_PC7") (pintype "bidirectional"))
    )
    (net (code "73") (name "unconnected-(U$9-PadPC8)") (class "Default")
      (node (ref "U$9") (pin "PC8") (pinfunction "PC8_PC8") (pintype "bidirectional"))
    )
    (net (code "74") (name "unconnected-(U$9-PadPC9)") (class "Default")
      (node (ref "U$9") (pin "PC9") (pinfunction "PC9_PC9") (pintype "bidirectional"))
    )
    (net (code "75") (name "unconnected-(U$9-PadPC11)") (class "Default")
      (node (ref "U$9") (pin "PC11") (pinfunction "PC11_PC11") (pintype "bidirectional"))
    )
    (net (code "76") (name "unconnected-(U$9-PadPC13)") (class "Default")
      (node (ref "U$9") (pin "PC13") (pinfunction "PC13_PC13") (pintype "bidirectional"))
    )
    (net (code "77") (name "unconnected-(U$9-PadPC14)") (class "Default")
      (node (ref "U$9") (pin "PC14") (pinfunction "PC14_PC14") (pintype "bidirectional"))
    )
    (net (code "78") (name "unconnected-(U$9-PadPC15)") (class "Default")
      (node (ref "U$9") (pin "PC15") (pinfunction "PC15_PC15") (pintype "bidirectional"))
    )
    (net (code "79") (name "unconnected-(U$9-PadPD2)") (class "Default")
      (node (ref "U$9") (pin "PD2") (pinfunction "PD2_PD2") (pintype "bidirectional"))
    )
    (net (code "80") (name "unconnected-(U$9-PadPH0)") (class "Default")
      (node (ref "U$9") (pin "PH0") (pinfunction "PH0_PH0") (pintype "bidirectional"))
    )
    (net (code "81") (name "unconnected-(U$9-PadPH1)") (class "Default")
      (node (ref "U$9") (pin "PH1") (pinfunction "PH1_PH1") (pintype "bidirectional"))
    )
    (net (code "82") (name "unconnected-(U7-FB{slash}NC-Pad7)") (class "Default")
      (node (ref "U7") (pin "7") (pinfunction "FB/NC_7") (pintype "passive"))
    )
    (net (code "83") (name "unconnected-(U7-IN_2-Pad3)") (class "Default")
      (node (ref "U7") (pin "3") (pinfunction "IN_2_3") (pintype "input"))
    )
    (net (code "84") (name "unconnected-(U7-OUT_2-Pad5)") (class "Default")
      (node (ref "U7") (pin "5") (pinfunction "OUT_2_5") (pintype "output"))
    )
    (net (code "85") (name "unconnected-(U7-~{RESET}-Pad8)") (class "Default")
      (node (ref "U7") (pin "8") (pinfunction "~{RESET}_8") (pintype "output"))
    )
  )
)
